# Main.net
KiCad netlist of a schematic drawn in Altium Designer
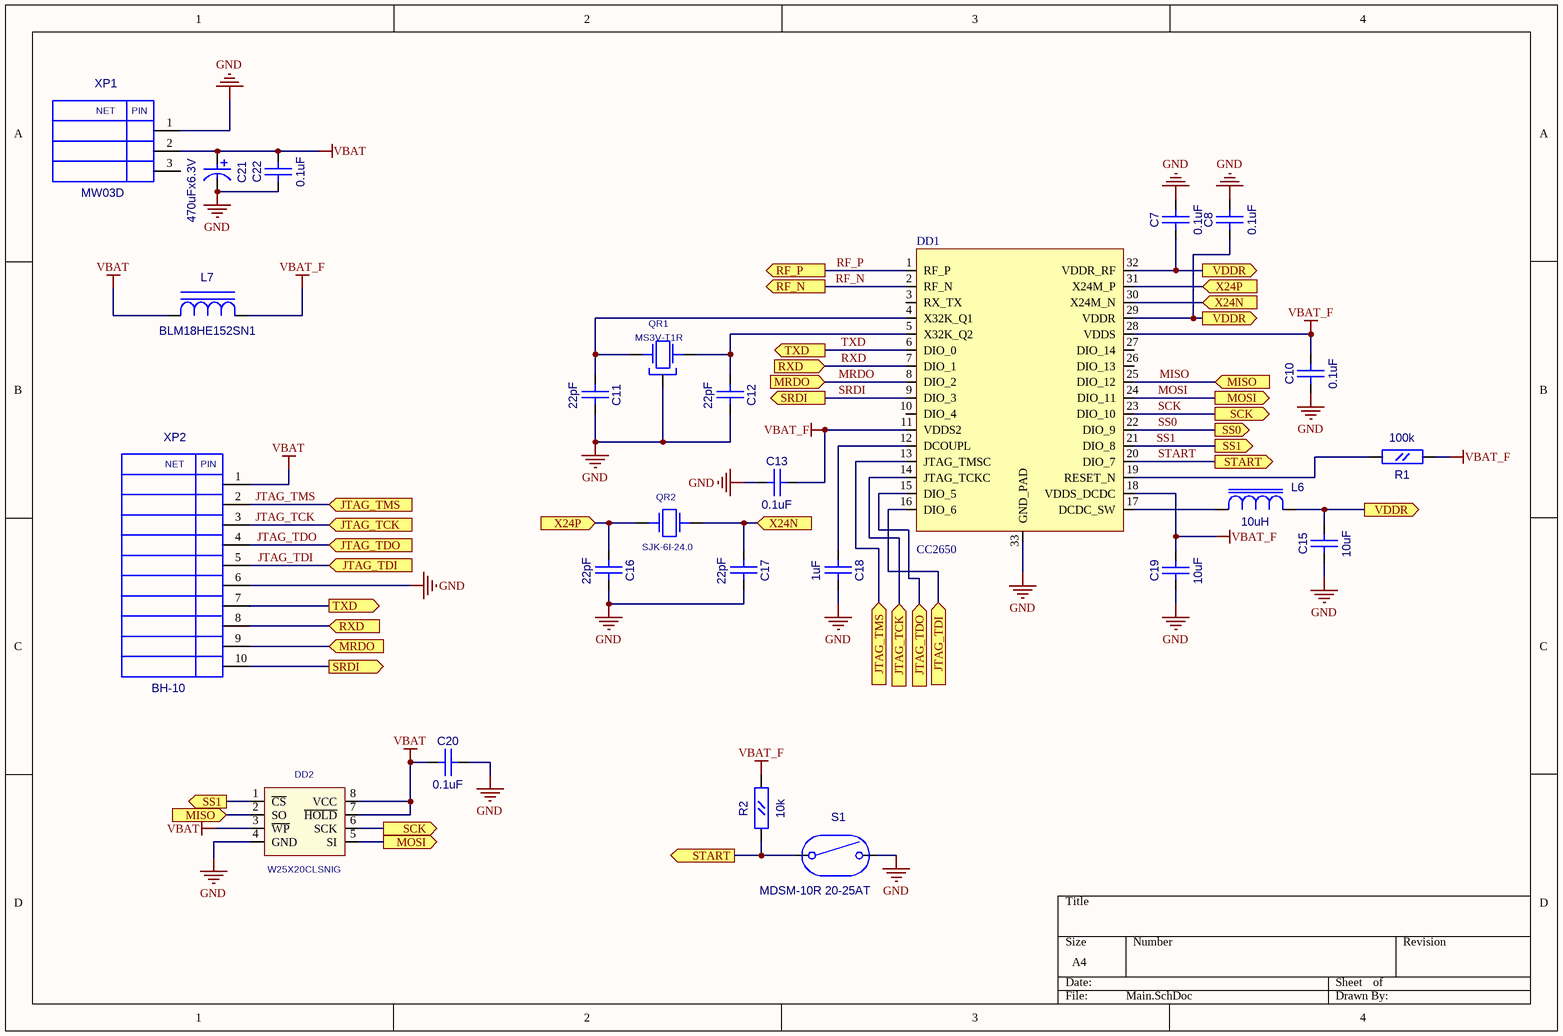
[diagram p0: Main.SchDoc]

(export (version "E")
  (design (tool "Eeschema 10.0.6"))
  (components
    (comp (ref "C7")
      (value "0.1uF")
      (footprint "CC0603")
      (description "CC0603")
      (libsource (lib "gprs_modem_2") (part "CC0603"))
    )
    (comp (ref "C8")
      (value "0.1uF")
      (footprint "CC0603")
      (description "CC0603")
      (libsource (lib "gprs_modem_2") (part "CC0603"))
    )
    (comp (ref "C10")
      (value "0.1uF")
      (footprint "CC0603")
      (description "CC0603")
      (libsource (lib "gprs_modem_2") (part "CC0603"))
    )
    (comp (ref "C11")
      (value "22pF")
      (footprint "CC0603")
      (description "CC0603")
      (libsource (lib "gprs_modem_2") (part "CC0603"))
    )
    (comp (ref "C12")
      (value "22pF")
      (footprint "CC0603")
      (description "CC0603")
      (libsource (lib "gprs_modem_2") (part "CC0603"))
    )
    (comp (ref "C13")
      (value "0.1uF")
      (footprint "CC0603")
      (description "CC0603")
      (libsource (lib "gprs_modem_2") (part "CC0603"))
    )
    (comp (ref "C15")
      (value "10uF")
      (footprint "CC0805")
      (description "CC0805")
      (libsource (lib "gprs_modem_2") (part "CC0805"))
    )
    (comp (ref "C16")
      (value "22pF")
      (footprint "CC0603")
      (description "CC0603")
      (libsource (lib "gprs_modem_2") (part "CC0603"))
    )
    (comp (ref "C17")
      (value "22pF")
      (footprint "CC0603")
      (description "CC0603")
      (libsource (lib "gprs_modem_2") (part "CC0603"))
    )
    (comp (ref "C18")
      (value "1uF")
      (footprint "CC0603")
      (description "CC0603")
      (libsource (lib "gprs_modem_2") (part "CC0603"))
    )
    (comp (ref "C19")
      (value "10uF")
      (footprint "CC0805")
      (description "CC0805")
      (libsource (lib "gprs_modem_2") (part "CC0805"))
    )
    (comp (ref "C20")
      (value "0.1uF")
      (footprint "CC0603")
      (description "CC0603")
      (libsource (lib "gprs_modem_2") (part "CC0603"))
    )
    (comp (ref "C21")
      (value "470uFx6.3V")
      (footprint "TAJ-D-1M")
      (description "TAJ-D")
      (libsource (lib "gprs_modem_2") (part "TAJ-D"))
    )
    (comp (ref "C22")
      (value "0.1uF")
      (footprint "CC0603")
      (description "CC0603")
      (libsource (lib "gprs_modem_2") (part "CC0603"))
    )
    (comp (ref "DD1")
      (value "CC2650")
      (footprint "QFN32_TI")
      (description "CC2650RHBT")
      (libsource (lib "gprs_modem_2") (part "CC2650RHB"))
    )
    (comp (ref "DD2")
      (value "W25X20CLSNIG")
      (footprint "EIAJ_SO8")
      (description "S25FL016A0LMFI01")
      (libsource (lib "gprs_modem_2") (part "S25FL016A0LMFI01"))
    )
    (comp (ref "L6")
      (value "10uH")
      (footprint "RC0805")
      (description "L0805")
      (libsource (lib "gprs_modem_2") (part "L0805"))
    )
    (comp (ref "L7")
      (value "BLM18HE152SN1")
      (footprint "L0603")
      (description "L0603")
      (libsource (lib "gprs_modem_2") (part "L0603"))
    )
    (comp (ref "QR1")
      (value "MS3V-T1R")
      (footprint "MS3V-T1R")
      (description "CRYSTAL_32768 Hz")
      (libsource (lib "gprs_modem_2") (part "MS3V-T1R"))
    )
    (comp (ref "QR2")
      (value "SJK-6I-24.0")
      (footprint "AC5032_2")
      (description "AC5032/2")
      (libsource (lib "gprs_modem_2") (part "AC5032_2"))
    )
    (comp (ref "R1")
      (value "100k")
      (footprint "RC0603")
      (description "RC0603")
      (libsource (lib "gprs_modem_2") (part "RC0603"))
    )
    (comp (ref "R2")
      (value "10k")
      (footprint "RC0603")
      (description "RC0603")
      (libsource (lib "gprs_modem_2") (part "RC0603"))
    )
    (comp (ref "S1")
      (value "MDSM-10R 20-25AT")
      (footprint "MDSM-10R")
      (description "Switch, Single Pole, Single Throw, Normally Open")
      (libsource (lib "gprs_modem") (part "MDSM-10R"))
    )
    (comp (ref "XP1") (value "MW03D") (footprint "MW03D") (libsource (lib "gprs_modem_2") (part "MW03D")))
    (comp (ref "XP2") (value "BH-10") (footprint "BH-10") (libsource (lib "gprs_modem_2") (part "BH-10")))
  )
  (nets
    (net (code "1") (name "/JTAG_TCK") (class "Default")
      (node (ref "DD1") (pin "14") (pinfunction "JTAG_TCKC_14") (pintype "passive"))
      (node (ref "XP2") (pin "3") (pinfunction "3_3") (pintype "passive"))
    )
    (net (code "2") (name "/JTAG_TDI") (class "Default")
      (node (ref "DD1") (pin "16") (pinfunction "DIO_6_16") (pintype "passive"))
      (node (ref "XP2") (pin "5") (pinfunction "5_5") (pintype "passive"))
    )
    (net (code "3") (name "/JTAG_TDO") (class "Default")
      (node (ref "DD1") (pin "15") (pinfunction "DIO_5_15") (pintype "passive"))
      (node (ref "XP2") (pin "4") (pinfunction "4_4") (pintype "passive"))
    )
    (net (code "4") (name "/JTAG_TMS") (class "Default")
      (node (ref "DD1") (pin "13") (pinfunction "JTAG_TMSC_13") (pintype "passive"))
      (node (ref "XP2") (pin "2") (pinfunction "2_2") (pintype "passive"))
    )
    (net (code "5") (name "/MISO") (class "Default")
      (node (ref "DD1") (pin "25") (pinfunction "DIO_12_25") (pintype "passive"))
      (node (ref "DD2") (pin "2") (pinfunction "SO_2") (pintype "passive"))
    )
    (net (code "6") (name "/MOSI") (class "Default")
      (node (ref "DD1") (pin "24") (pinfunction "DIO_11_24") (pintype "passive"))
      (node (ref "DD2") (pin "5") (pinfunction "SI_5") (pintype "passive"))
    )
    (net (code "7") (name "/MRDO") (class "Default")
      (node (ref "DD1") (pin "8") (pinfunction "DIO_2_8") (pintype "passive"))
      (node (ref "XP2") (pin "9") (pinfunction "9_9") (pintype "passive"))
    )
    (net (code "8") (name "/RF_N") (class "Default")
      (node (ref "DD1") (pin "2") (pinfunction "RF_N_2") (pintype "passive"))
    )
    (net (code "9") (name "/RF_P") (class "Default")
      (node (ref "DD1") (pin "1") (pinfunction "RF_P_1") (pintype "passive"))
    )
    (net (code "10") (name "/RXD") (class "Default")
      (node (ref "DD1") (pin "7") (pinfunction "DIO_1_7") (pintype "passive"))
      (node (ref "XP2") (pin "8") (pinfunction "8_8") (pintype "passive"))
    )
    (net (code "11") (name "/SCK") (class "Default")
      (node (ref "DD1") (pin "23") (pinfunction "DIO_10_23") (pintype "passive"))
      (node (ref "DD2") (pin "6") (pinfunction "SCK_6") (pintype "passive"))
    )
    (net (code "12") (name "/SRDI") (class "Default")
      (node (ref "DD1") (pin "9") (pinfunction "DIO_3_9") (pintype "passive"))
      (node (ref "XP2") (pin "10") (pinfunction "10_10") (pintype "passive"))
    )
    (net (code "13") (name "/SS0") (class "Default")
      (node (ref "DD1") (pin "22") (pinfunction "DIO_9_22") (pintype "passive"))
    )
    (net (code "14") (name "/SS1") (class "Default")
      (node (ref "DD1") (pin "21") (pinfunction "DIO_8_21") (pintype "passive"))
      (node (ref "DD2") (pin "1") (pinfunction "~{CS}_1") (pintype "passive"))
    )
    (net (code "15") (name "/START") (class "Default")
      (node (ref "DD1") (pin "20") (pinfunction "DIO_7_20") (pintype "passive"))
      (node (ref "R2") (pin "1") (pinfunction "A_1") (pintype "passive"))
      (node (ref "S1") (pin "1") (pinfunction "1_1") (pintype "passive"))
    )
    (net (code "16") (name "/TXD") (class "Default")
      (node (ref "DD1") (pin "6") (pinfunction "DIO_0_6") (pintype "passive"))
      (node (ref "XP2") (pin "7") (pinfunction "7_7") (pintype "passive"))
    )
    (net (code "17") (name "/VDDR") (class "Default")
      (node (ref "C15") (pin "2") (pinfunction "B_2") (pintype "passive"))
      (node (ref "C7") (pin "1") (pinfunction "A_1") (pintype "passive"))
      (node (ref "C8") (pin "1") (pinfunction "A_1") (pintype "passive"))
      (node (ref "DD1") (pin "29") (pinfunction "VDDR_29") (pintype "passive"))
      (node (ref "DD1") (pin "32") (pinfunction "VDDR_RF_32") (pintype "passive"))
      (node (ref "L6") (pin "2") (pinfunction "B_2") (pintype "passive"))
    )
    (net (code "18") (name "/X24N") (class "Default")
      (node (ref "C17") (pin "1") (pinfunction "A_1") (pintype "passive"))
      (node (ref "DD1") (pin "30") (pinfunction "X24M_N_30") (pintype "passive"))
      (node (ref "QR2") (pin "2") (pintype "passive"))
    )
    (net (code "19") (name "/X24P") (class "Default")
      (node (ref "C16") (pin "1") (pinfunction "A_1") (pintype "passive"))
      (node (ref "DD1") (pin "31") (pinfunction "X24M_P_31") (pintype "passive"))
      (node (ref "QR2") (pin "1") (pintype "passive"))
    )
    (net (code "20") (name "GND") (class "Default")
      (node (ref "C10") (pin "1") (pinfunction "A_1") (pintype "passive"))
      (node (ref "C11") (pin "2") (pinfunction "B_2") (pintype "passive"))
      (node (ref "C12") (pin "2") (pinfunction "B_2") (pintype "passive"))
      (node (ref "C13") (pin "1") (pinfunction "A_1") (pintype "passive"))
      (node (ref "C15") (pin "1") (pinfunction "A_1") (pintype "passive"))
      (node (ref "C16") (pin "2") (pinfunction "B_2") (pintype "passive"))
      (node (ref "C17") (pin "2") (pinfunction "B_2") (pintype "passive"))
      (node (ref "C18") (pin "2") (pinfunction "B_2") (pintype "passive"))
      (node (ref "C19") (pin "1") (pinfunction "A_1") (pintype "passive"))
      (node (ref "C20") (pin "2") (pinfunction "B_2") (pintype "passive"))
      (node (ref "C21") (pin "2") (pinfunction "B_2") (pintype "passive"))
      (node (ref "C22") (pin "1") (pinfunction "A_1") (pintype "passive"))
      (node (ref "C7") (pin "2") (pinfunction "B_2") (pintype "passive"))
      (node (ref "C8") (pin "2") (pinfunction "B_2") (pintype "passive"))
      (node (ref "DD1") (pin "33") (pinfunction "GND_PAD_33") (pintype "passive"))
      (node (ref "DD2") (pin "4") (pinfunction "GND_4") (pintype "passive"))
      (node (ref "QR1") (pin "3") (pinfunction "3_3") (pintype "passive"))
      (node (ref "S1") (pin "2") (pinfunction "2_2") (pintype "passive"))
      (node (ref "XP1") (pin "1") (pinfunction "1_1") (pintype "passive"))
      (node (ref "XP2") (pin "6") (pinfunction "6_6") (pintype "passive"))
    )
    (net (code "21") (name "Net-(C11-A)") (class "Default")
      (node (ref "C11") (pin "1") (pinfunction "A_1") (pintype "passive"))
      (node (ref "DD1") (pin "4") (pinfunction "X32K_Q1_4") (pintype "passive"))
      (node (ref "QR1") (pin "2") (pinfunction "X2_2") (pintype "passive"))
    )
    (net (code "22") (name "Net-(C12-A)") (class "Default")
      (node (ref "C12") (pin "1") (pinfunction "A_1") (pintype "passive"))
      (node (ref "DD1") (pin "5") (pinfunction "X32K_Q2_5") (pintype "passive"))
      (node (ref "QR1") (pin "1") (pinfunction "X1_1") (pintype "passive"))
    )
    (net (code "23") (name "Net-(C18-A)") (class "Default")
      (node (ref "C18") (pin "1") (pinfunction "A_1") (pintype "passive"))
      (node (ref "DD1") (pin "12") (pinfunction "DCOUPL_12") (pintype "passive"))
    )
    (net (code "24") (name "Net-(DD1-DCDC_SW)") (class "Default")
      (node (ref "DD1") (pin "17") (pinfunction "DCDC_SW_17") (pintype "passive"))
      (node (ref "L6") (pin "1") (pinfunction "A_1") (pintype "passive"))
    )
    (net (code "25") (name "Net-(DD1-RESET_N)") (class "Default")
      (node (ref "DD1") (pin "19") (pinfunction "RESET_N_19") (pintype "passive"))
      (node (ref "R1") (pin "2") (pinfunction "B_2") (pintype "passive"))
    )
    (net (code "26") (name "VBAT") (class "Default")
      (node (ref "C20") (pin "1") (pinfunction "A_1") (pintype "passive"))
      (node (ref "C21") (pin "1") (pinfunction "A_1") (pintype "passive"))
      (node (ref "C22") (pin "2") (pinfunction "B_2") (pintype "passive"))
      (node (ref "DD2") (pin "3") (pinfunction "~{WP}_3") (pintype "passive"))
      (node (ref "DD2") (pin "7") (pinfunction "~{HOLD}_7") (pintype "passive"))
      (node (ref "DD2") (pin "8") (pinfunction "VCC_8") (pintype "passive"))
      (node (ref "L7") (pin "1") (pinfunction "A_1") (pintype "passive"))
      (node (ref "XP1") (pin "2") (pinfunction "2_2") (pintype "passive"))
      (node (ref "XP2") (pin "1") (pinfunction "1_1") (pintype "passive"))
    )
    (net (code "27") (name "VBAT_F") (class "Default")
      (node (ref "C10") (pin "2") (pinfunction "B_2") (pintype "passive"))
      (node (ref "C13") (pin "2") (pinfunction "B_2") (pintype "passive"))
      (node (ref "C19") (pin "2") (pinfunction "B_2") (pintype "passive"))
      (node (ref "DD1") (pin "11") (pinfunction "VDDS2_11") (pintype "passive"))
      (node (ref "DD1") (pin "18") (pinfunction "VDDS_DCDC_18") (pintype "passive"))
      (node (ref "DD1") (pin "28") (pinfunction "VDDS_28") (pintype "passive"))
      (node (ref "L7") (pin "2") (pinfunction "C_2") (pintype "passive"))
      (node (ref "R1") (pin "1") (pinfunction "A_1") (pintype "passive"))
      (node (ref "R2") (pin "2") (pinfunction "B_2") (pintype "passive"))
    )
    (net (code "28") (name "unconnected-(DD1-DIO_4-Pad10)") (class "Default")
      (node (ref "DD1") (pin "10") (pinfunction "DIO_4_10") (pintype "passive"))
    )
    (net (code "29") (name "unconnected-(DD1-DIO_13-Pad26)") (class "Default")
      (node (ref "DD1") (pin "26") (pinfunction "DIO_13_26") (pintype "passive"))
    )
    (net (code "30") (name "unconnected-(DD1-DIO_14-Pad27)") (class "Default")
      (node (ref "DD1") (pin "27") (pinfunction "DIO_14_27") (pintype "passive"))
    )
    (net (code "31") (name "unconnected-(DD1-RX_TX-Pad3)") (class "Default")
      (node (ref "DD1") (pin "3") (pinfunction "RX_TX_3") (pintype "passive"))
    )
    (net (code "32") (name "unconnected-(XP1-Pad3)") (class "Default")
      (node (ref "XP1") (pin "3") (pinfunction "3_3") (pintype "passive"))
    )
  )
)
